# TribeBot21.net
KiCad netlist of a schematic drawn in EAGLE
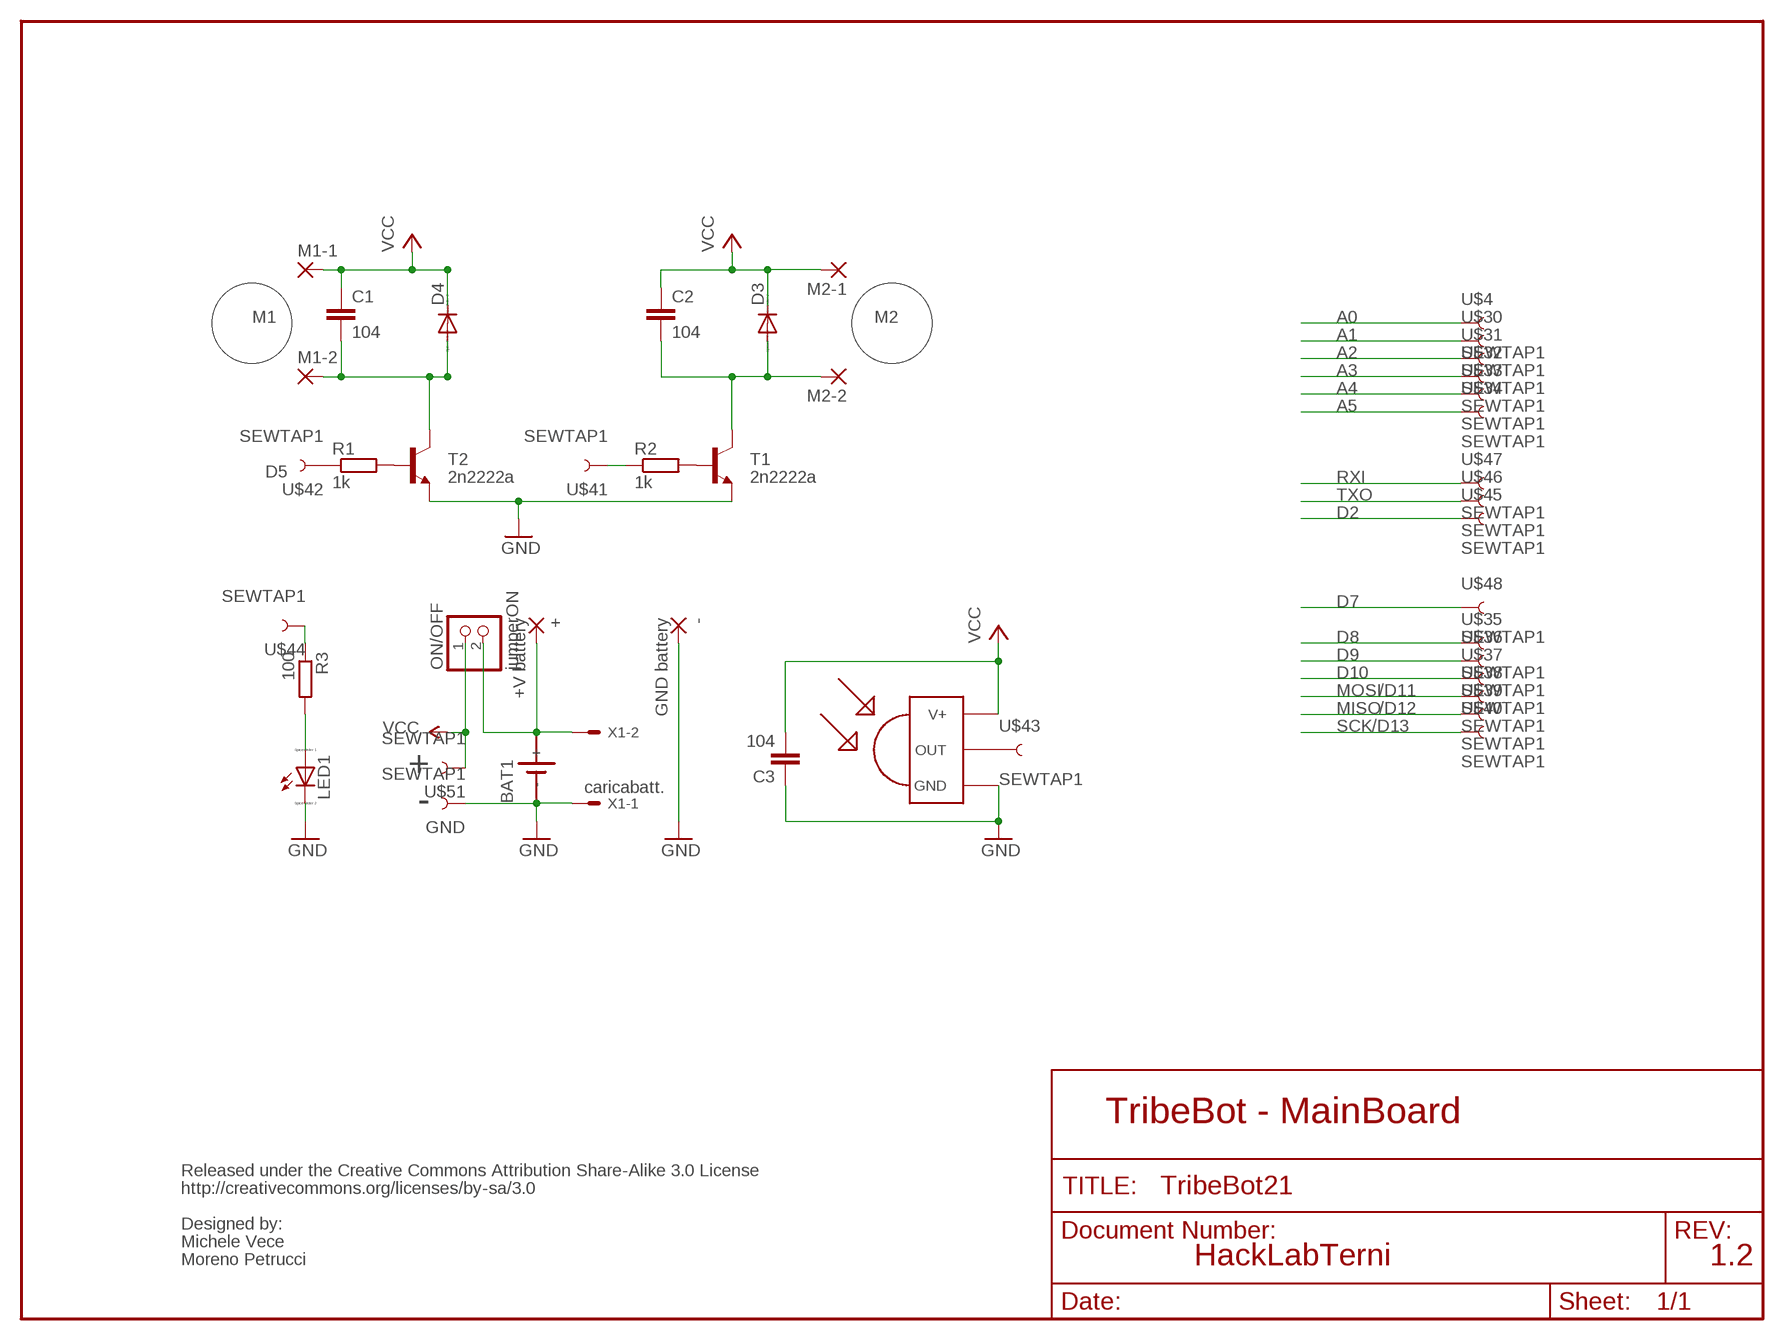
[diagram p0: schematic, sheet 1]

(export (version "E")
  (design (tool "Eeschema 10.0.6"))
  (components
    (comp (ref "+")
      (value "+V battery")
      (footprint "eagle-import:2,15_1,0")
      (libsource (lib "eagle-import") (part "2,15/1,0"))
    )
    (comp (ref "-")
      (value "GND battery")
      (footprint "eagle-import:2,15_1,0")
      (libsource (lib "eagle-import") (part "2,15/1,0"))
    )
    (comp (ref "BAT1")
      (value "SN2032")
      (footprint "eagle-import:SN2032")
      (libsource (lib "eagle-import") (part "SN2032"))
    )
    (comp (ref "C1")
      (value "104")
      (footprint "eagle-import:C2.5-2")
      (libsource (lib "eagle-import") (part "C2.5/2"))
    )
    (comp (ref "C2")
      (value "104")
      (footprint "eagle-import:C2.5-2")
      (libsource (lib "eagle-import") (part "C2.5/2"))
    )
    (comp (ref "C3")
      (value "104")
      (footprint "eagle-import:C2.5-2")
      (libsource (lib "eagle-import") (part "C2.5/2"))
    )
    (comp (ref "D3")
      (value "1N4148DO35-7")
      (footprint "eagle-import:DO35-7")
      (libsource (lib "eagle-import") (part "1N4148DO35-7"))
    )
    (comp (ref "D4")
      (value "1N4148DO35-7")
      (footprint "eagle-import:DO35-7")
      (libsource (lib "eagle-import") (part "1N4148DO35-7"))
    )
    (comp (ref "GND")
      (value "SEWTAP1")
      (footprint "eagle-import:PETAL-LONG-1")
      (libsource (lib "eagle-import") (part "SEWTAP1"))
    )
    (comp (ref "LED1")
      (value "LED_ELD260")
      (footprint "eagle-import:LED_LD260")
      (libsource (lib "eagle-import") (part "LED_ELD260"))
    )
    (comp (ref "M1-1")
      (value "1,6/0,8")
      (footprint "eagle-import:1,6_0,8")
      (libsource (lib "eagle-import") (part "1,6/0,8"))
    )
    (comp (ref "M1-2")
      (value "1,6/0,8")
      (footprint "eagle-import:1,6_0,8")
      (libsource (lib "eagle-import") (part "1,6/0,8"))
    )
    (comp (ref "M2-1")
      (value "1,6/0,8")
      (footprint "eagle-import:1,6_0,8")
      (libsource (lib "eagle-import") (part "1,6/0,8"))
    )
    (comp (ref "M2-2")
      (value "1,6/0,8")
      (footprint "eagle-import:1,6_0,8")
      (libsource (lib "eagle-import") (part "1,6/0,8"))
    )
    (comp (ref "ON/OFF")
      (value "jumperON")
      (footprint "eagle-import:1X02")
      (libsource (lib "eagle-import") (part "PINHD-1X2"))
    )
    (comp (ref "R1")
      (value "1k")
      (footprint "eagle-import:0204_7")
      (libsource (lib "eagle-import") (part "R-EU_0204/7"))
    )
    (comp (ref "R2")
      (value "1k")
      (footprint "eagle-import:0204_7")
      (libsource (lib "eagle-import") (part "R-EU_0204/7"))
    )
    (comp (ref "R3")
      (value "100")
      (footprint "eagle-import:0204_7")
      (libsource (lib "eagle-import") (part "R-EU_0204/7"))
    )
    (comp (ref "T1")
      (value "2n2222a")
      (footprint "eagle-import:TO-92")
      (libsource (lib "eagle-import") (part "TRANSISTOR_NPNTO92"))
    )
    (comp (ref "T2")
      (value "2n2222a")
      (footprint "eagle-import:TO-92")
      (libsource (lib "eagle-import") (part "TRANSISTOR_NPNTO92"))
    )
    (comp (ref "U$1")
      (value "TSOP4838")
      (footprint "eagle-import:TSOP18XX")
      (libsource (lib "eagle-import") (part "TSOP4838"))
    )
    (comp (ref "U$4")
      (value "SEWTAP1")
      (footprint "eagle-import:PETAL-LONG-1")
      (libsource (lib "eagle-import") (part "SEWTAP1"))
    )
    (comp (ref "U$30")
      (value "SEWTAP1")
      (footprint "eagle-import:PETAL-LONG-1")
      (libsource (lib "eagle-import") (part "SEWTAP1"))
    )
    (comp (ref "U$31")
      (value "SEWTAP1")
      (footprint "eagle-import:PETAL-LONG-1")
      (libsource (lib "eagle-import") (part "SEWTAP1"))
    )
    (comp (ref "U$32")
      (value "SEWTAP1")
      (footprint "eagle-import:PETAL-LONG-1")
      (libsource (lib "eagle-import") (part "SEWTAP1"))
    )
    (comp (ref "U$33")
      (value "SEWTAP1")
      (footprint "eagle-import:PETAL-LONG-1")
      (libsource (lib "eagle-import") (part "SEWTAP1"))
    )
    (comp (ref "U$34")
      (value "SEWTAP1")
      (footprint "eagle-import:PETAL-LONG-1")
      (libsource (lib "eagle-import") (part "SEWTAP1"))
    )
    (comp (ref "U$35")
      (value "SEWTAP1")
      (footprint "eagle-import:PETAL-LONG-1")
      (libsource (lib "eagle-import") (part "SEWTAP1"))
    )
    (comp (ref "U$36")
      (value "SEWTAP1")
      (footprint "eagle-import:PETAL-LONG-1")
      (libsource (lib "eagle-import") (part "SEWTAP1"))
    )
    (comp (ref "U$37")
      (value "SEWTAP1")
      (footprint "eagle-import:PETAL-LONG-1")
      (libsource (lib "eagle-import") (part "SEWTAP1"))
    )
    (comp (ref "U$38")
      (value "SEWTAP1")
      (footprint "eagle-import:PETAL-LONG-1")
      (libsource (lib "eagle-import") (part "SEWTAP1"))
    )
    (comp (ref "U$39")
      (value "SEWTAP1")
      (footprint "eagle-import:PETAL-LONG-1")
      (libsource (lib "eagle-import") (part "SEWTAP1"))
    )
    (comp (ref "U$40")
      (value "SEWTAP1")
      (footprint "eagle-import:PETAL-LONG-1")
      (libsource (lib "eagle-import") (part "SEWTAP1"))
    )
    (comp (ref "U$41")
      (value "SEWTAP1")
      (footprint "eagle-import:PETAL-LONG-1")
      (libsource (lib "eagle-import") (part "SEWTAP1"))
    )
    (comp (ref "U$42")
      (value "SEWTAP1")
      (footprint "eagle-import:PETAL-LONG-1")
      (libsource (lib "eagle-import") (part "SEWTAP1"))
    )
    (comp (ref "U$43")
      (value "SEWTAP1")
      (footprint "eagle-import:PETAL-LONG-1")
      (libsource (lib "eagle-import") (part "SEWTAP1"))
    )
    (comp (ref "U$44")
      (value "SEWTAP1")
      (footprint "eagle-import:PETAL-LONG-1")
      (libsource (lib "eagle-import") (part "SEWTAP1"))
    )
    (comp (ref "U$45")
      (value "SEWTAP1")
      (footprint "eagle-import:PETAL-LONG-1")
      (libsource (lib "eagle-import") (part "SEWTAP1"))
    )
    (comp (ref "U$46")
      (value "SEWTAP1")
      (footprint "eagle-import:PETAL-LONG-1")
      (libsource (lib "eagle-import") (part "SEWTAP1"))
    )
    (comp (ref "U$47")
      (value "SEWTAP1")
      (footprint "eagle-import:PETAL-LONG-1")
      (libsource (lib "eagle-import") (part "SEWTAP1"))
    )
    (comp (ref "U$48")
      (value "SEWTAP1")
      (footprint "eagle-import:PETAL-LONG-1")
      (libsource (lib "eagle-import") (part "SEWTAP1"))
    )
    (comp (ref "U$51")
      (value "SEWTAP1")
      (footprint "eagle-import:PETAL-LONG-1")
      (libsource (lib "eagle-import") (part "SEWTAP1"))
    )
    (comp (ref "X1")
      (value "caricabatt.")
      (footprint "eagle-import:22-23-2021")
      (fields (field (name "MF") "MOLEX") (field (name "MPN") "22-23-2021"))
      (libsource (lib "eagle-import") (part "22-23-2021"))
    )
  )
  (nets
    (net (code "1") (name "/A0") (class "Default")
      (node (ref "U$4") (pin "1") (pinfunction "1_1") (pintype "bidirectional"))
    )
    (net (code "2") (name "/A1") (class "Default")
      (node (ref "U$30") (pin "1") (pinfunction "1_1") (pintype "bidirectional"))
    )
    (net (code "3") (name "/A2") (class "Default")
      (node (ref "U$31") (pin "1") (pinfunction "1_1") (pintype "bidirectional"))
    )
    (net (code "4") (name "/A3") (class "Default")
      (node (ref "U$32") (pin "1") (pinfunction "1_1") (pintype "bidirectional"))
    )
    (net (code "5") (name "/A4") (class "Default")
      (node (ref "U$33") (pin "1") (pinfunction "1_1") (pintype "bidirectional"))
    )
    (net (code "6") (name "/A5") (class "Default")
      (node (ref "U$34") (pin "1") (pinfunction "1_1") (pintype "bidirectional"))
    )
    (net (code "7") (name "/D2") (class "Default")
      (node (ref "U$45") (pin "1") (pinfunction "1_1") (pintype "bidirectional"))
    )
    (net (code "8") (name "/D7") (class "Default")
      (node (ref "U$48") (pin "1") (pinfunction "1_1") (pintype "bidirectional"))
    )
    (net (code "9") (name "/D8") (class "Default")
      (node (ref "U$35") (pin "1") (pinfunction "1_1") (pintype "bidirectional"))
    )
    (net (code "10") (name "/D9") (class "Default")
      (node (ref "U$36") (pin "1") (pinfunction "1_1") (pintype "bidirectional"))
    )
    (net (code "11") (name "/D10") (class "Default")
      (node (ref "U$37") (pin "1") (pinfunction "1_1") (pintype "bidirectional"))
    )
    (net (code "12") (name "/MISO") (class "Default")
      (node (ref "U$39") (pin "1") (pinfunction "1_1") (pintype "bidirectional"))
    )
    (net (code "13") (name "/MOSI") (class "Default")
      (node (ref "U$38") (pin "1") (pinfunction "1_1") (pintype "bidirectional"))
    )
    (net (code "14") (name "/RXI") (class "Default")
      (node (ref "U$47") (pin "1") (pinfunction "1_1") (pintype "bidirectional"))
    )
    (net (code "15") (name "/SCK") (class "Default")
      (node (ref "U$40") (pin "1") (pinfunction "1_1") (pintype "bidirectional"))
    )
    (net (code "16") (name "/TXO") (class "Default")
      (node (ref "U$46") (pin "1") (pinfunction "1_1") (pintype "bidirectional"))
    )
    (net (code "17") (name "GND") (class "Default")
      (node (ref "-") (pin "1") (pinfunction "P_1") (pintype "passive"))
      (node (ref "BAT1") (pin "-") (pinfunction "-_-") (pintype "passive"))
      (node (ref "C3") (pin "1") (pinfunction "1_1") (pintype "passive"))
      (node (ref "GND") (pin "1") (pinfunction "1_1") (pintype "bidirectional"))
      (node (ref "LED1") (pin "K") (pinfunction "C_K") (pintype "passive"))
      (node (ref "T1") (pin "1") (pinfunction "E_1") (pintype "passive"))
      (node (ref "T2") (pin "1") (pinfunction "E_1") (pintype "passive"))
      (node (ref "U$1") (pin "GND") (pinfunction "GND_GND") (pintype "bidirectional"))
      (node (ref "X1") (pin "1") (pinfunction "S_1") (pintype "passive"))
    )
    (net (code "18") (name "Net-(+-P)") (class "Default")
      (node (ref "+") (pin "1") (pinfunction "P_1") (pintype "passive"))
      (node (ref "BAT1") (pin "+") (pinfunction "+_+") (pintype "passive"))
      (node (ref "ON/OFF") (pin "2") (pinfunction "2_2") (pintype "passive"))
      (node (ref "X1") (pin "2") (pinfunction "S_2") (pintype "passive"))
    )
    (net (code "19") (name "Net-(LED1-PadA)") (class "Default")
      (node (ref "LED1") (pin "A") (pinfunction "A_A") (pintype "passive"))
      (node (ref "R3") (pin "2") (pinfunction "2_2") (pintype "passive"))
    )
    (net (code "20") (name "Net-(M1-2-P)") (class "Default")
      (node (ref "C1") (pin "2") (pinfunction "2_2") (pintype "passive"))
      (node (ref "D4") (pin "A") (pinfunction "A_A") (pintype "passive"))
      (node (ref "M1-2") (pin "1") (pinfunction "P_1") (pintype "passive"))
      (node (ref "T2") (pin "3") (pinfunction "C_3") (pintype "passive"))
    )
    (net (code "21") (name "Net-(M2-2-P)") (class "Default")
      (node (ref "C2") (pin "2") (pinfunction "2_2") (pintype "passive"))
      (node (ref "D3") (pin "A") (pinfunction "A_A") (pintype "passive"))
      (node (ref "M2-2") (pin "1") (pinfunction "P_1") (pintype "passive"))
      (node (ref "T1") (pin "3") (pinfunction "C_3") (pintype "passive"))
    )
    (net (code "22") (name "Net-(R1-Pad1)") (class "Default")
      (node (ref "R1") (pin "1") (pinfunction "1_1") (pintype "passive"))
      (node (ref "U$42") (pin "1") (pinfunction "1_1") (pintype "bidirectional"))
    )
    (net (code "23") (name "Net-(R2-Pad1)") (class "Default")
      (node (ref "R2") (pin "1") (pinfunction "1_1") (pintype "passive"))
      (node (ref "U$41") (pin "1") (pinfunction "1_1") (pintype "bidirectional"))
    )
    (net (code "24") (name "Net-(R3-Pad1)") (class "Default")
      (node (ref "R3") (pin "1") (pinfunction "1_1") (pintype "passive"))
      (node (ref "U$44") (pin "1") (pinfunction "1_1") (pintype "bidirectional"))
    )
    (net (code "25") (name "Net-(T1-B)") (class "Default")
      (node (ref "R2") (pin "2") (pinfunction "2_2") (pintype "passive"))
      (node (ref "T1") (pin "2") (pinfunction "B_2") (pintype "passive"))
    )
    (net (code "26") (name "Net-(T2-B)") (class "Default")
      (node (ref "R1") (pin "2") (pinfunction "2_2") (pintype "passive"))
      (node (ref "T2") (pin "2") (pinfunction "B_2") (pintype "passive"))
    )
    (net (code "27") (name "Net-(U$1-PadOUT)") (class "Default")
      (node (ref "U$1") (pin "OUT") (pinfunction "OUT_OUT") (pintype "bidirectional"))
      (node (ref "U$43") (pin "1") (pinfunction "1_1") (pintype "bidirectional"))
    )
    (net (code "28") (name "VCC") (class "Default")
      (node (ref "C1") (pin "1") (pinfunction "1_1") (pintype "passive"))
      (node (ref "C2") (pin "1") (pinfunction "1_1") (pintype "passive"))
      (node (ref "C3") (pin "2") (pinfunction "2_2") (pintype "passive"))
      (node (ref "D3") (pin "C") (pinfunction "C_C") (pintype "passive"))
      (node (ref "D4") (pin "C") (pinfunction "C_C") (pintype "passive"))
      (node (ref "M1-1") (pin "1") (pinfunction "P_1") (pintype "passive"))
      (node (ref "M2-1") (pin "1") (pinfunction "P_1") (pintype "passive"))
      (node (ref "ON/OFF") (pin "1") (pinfunction "1_1") (pintype "passive"))
      (node (ref "U$1") (pin "VCC") (pinfunction "V+_VCC") (pintype "bidirectional"))
      (node (ref "U$51") (pin "1") (pinfunction "1_1") (pintype "bidirectional"))
    )
  )
)
